# Sheet1.net
KiCad netlist of a schematic drawn in Altium Designer
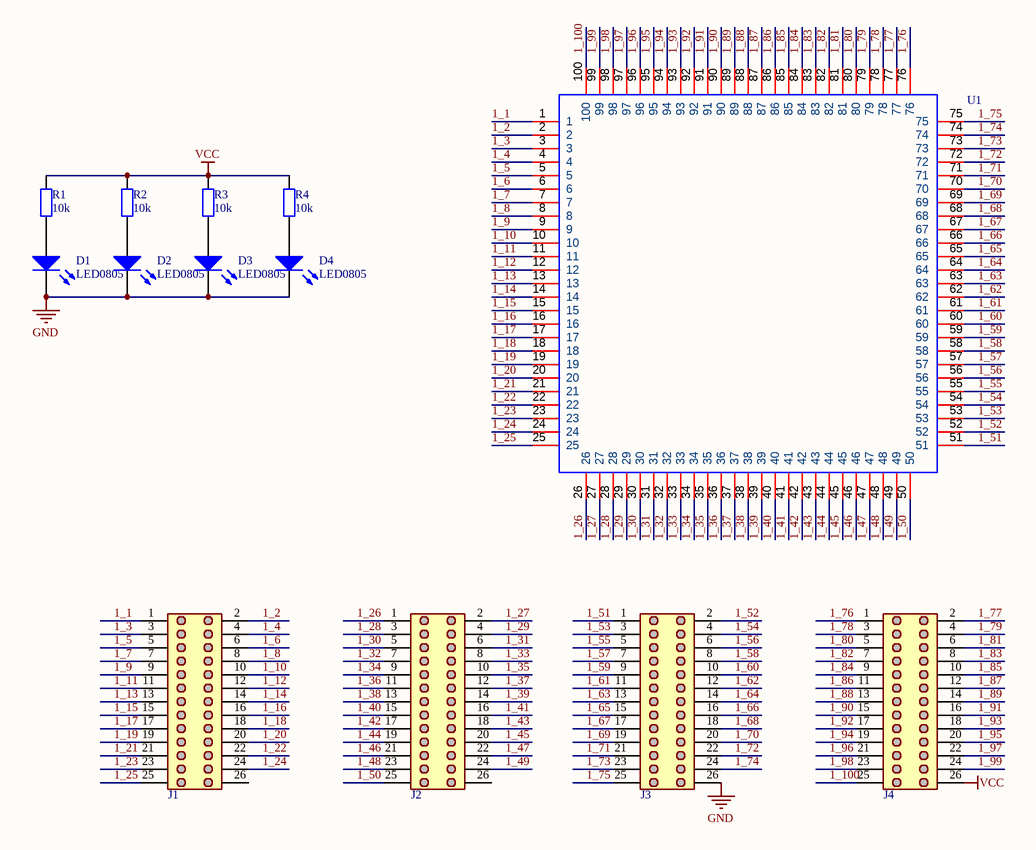
[diagram p0: Sheet1.SchDoc]

(export (version "E")
  (design (tool "Eeschema 10.0.6"))
  (components
    (comp (ref "D1") (value "LED0805") (footprint "L0805RED") (libsource (lib "SMDLibrary") (part "LED0805")))
    (comp (ref "D2") (value "LED0805") (footprint "L0805RED") (libsource (lib "SMDLibrary") (part "LED0805")))
    (comp (ref "D3") (value "LED0805") (footprint "L0805RED") (libsource (lib "SMDLibrary") (part "LED0805")))
    (comp (ref "D4") (value "LED0805") (footprint "L0805RED") (libsource (lib "SMDLibrary") (part "LED0805")))
    (comp (ref "J1")
      (value "Header 13x2 TH Pitch 2.54mm")
      (footprint "Header 13x2 TH Pitch 2.54mm")
      (libsource (lib "SMDLibrary") (part "Header 13x2 TH Pitch 2.54mm"))
    )
    (comp (ref "J2")
      (value "Header 13x2 TH Pitch 2.54mm")
      (footprint "Header 13x2 TH Pitch 2.54mm")
      (libsource (lib "SMDLibrary") (part "Header 13x2 TH Pitch 2.54mm"))
    )
    (comp (ref "J3")
      (value "Header 13x2 TH Pitch 2.54mm")
      (footprint "Header 13x2 TH Pitch 2.54mm")
      (libsource (lib "SMDLibrary") (part "Header 13x2 TH Pitch 2.54mm"))
    )
    (comp (ref "J4")
      (value "Header 13x2 TH Pitch 2.54mm")
      (footprint "Header 13x2 TH Pitch 2.54mm")
      (libsource (lib "SMDLibrary") (part "Header 13x2 TH Pitch 2.54mm"))
    )
    (comp (ref "R1") (value "10k") (footprint "R0805") (libsource (lib "SMDLibrary") (part "Resistor")))
    (comp (ref "R2") (value "10k") (footprint "R0805") (libsource (lib "SMDLibrary") (part "Resistor")))
    (comp (ref "R3") (value "10k") (footprint "R0805") (libsource (lib "SMDLibrary") (part "Resistor")))
    (comp (ref "R4") (value "10k") (footprint "R0805") (libsource (lib "SMDLibrary") (part "Resistor")))
    (comp (ref "U1")
      (value "QFP100-0.5 SOCKET")
      (footprint "QFP100-0.5 SOCKET")
      (libsource (lib "SMDLibrary") (part "QFP100-0.5 SOCKET"))
    )
  )
  (nets
    (net (code "1") (name "/1_1") (class "Default")
      (node (ref "J1") (pin "1") (pinfunction "1_1") (pintype "passive"))
      (node (ref "U1") (pin "1") (pinfunction "1_1") (pintype "passive"))
    )
    (net (code "2") (name "/1_2") (class "Default")
      (node (ref "J1") (pin "2") (pinfunction "2_2") (pintype "passive"))
      (node (ref "U1") (pin "2") (pinfunction "2_2") (pintype "passive"))
    )
    (net (code "3") (name "/1_3") (class "Default")
      (node (ref "J1") (pin "3") (pinfunction "3_3") (pintype "passive"))
      (node (ref "U1") (pin "3") (pinfunction "3_3") (pintype "passive"))
    )
    (net (code "4") (name "/1_4") (class "Default")
      (node (ref "J1") (pin "4") (pinfunction "4_4") (pintype "passive"))
      (node (ref "U1") (pin "4") (pinfunction "4_4") (pintype "passive"))
    )
    (net (code "5") (name "/1_5") (class "Default")
      (node (ref "J1") (pin "5") (pinfunction "5_5") (pintype "passive"))
      (node (ref "U1") (pin "5") (pinfunction "5_5") (pintype "passive"))
    )
    (net (code "6") (name "/1_6") (class "Default")
      (node (ref "J1") (pin "6") (pinfunction "6_6") (pintype "passive"))
      (node (ref "U1") (pin "6") (pinfunction "6_6") (pintype "passive"))
    )
    (net (code "7") (name "/1_7") (class "Default")
      (node (ref "J1") (pin "7") (pinfunction "7_7") (pintype "passive"))
      (node (ref "U1") (pin "7") (pinfunction "7_7") (pintype "passive"))
    )
    (net (code "8") (name "/1_8") (class "Default")
      (node (ref "J1") (pin "8") (pinfunction "8_8") (pintype "passive"))
      (node (ref "U1") (pin "8") (pinfunction "8_8") (pintype "passive"))
    )
    (net (code "9") (name "/1_9") (class "Default")
      (node (ref "J1") (pin "9") (pinfunction "9_9") (pintype "passive"))
      (node (ref "U1") (pin "9") (pinfunction "9_9") (pintype "passive"))
    )
    (net (code "10") (name "/1_10") (class "Default")
      (node (ref "J1") (pin "10") (pinfunction "10_10") (pintype "passive"))
      (node (ref "U1") (pin "10") (pinfunction "10_10") (pintype "passive"))
    )
    (net (code "11") (name "/1_11") (class "Default")
      (node (ref "J1") (pin "11") (pinfunction "11_11") (pintype "passive"))
      (node (ref "U1") (pin "11") (pinfunction "11_11") (pintype "passive"))
    )
    (net (code "12") (name "/1_12") (class "Default")
      (node (ref "J1") (pin "12") (pinfunction "12_12") (pintype "passive"))
      (node (ref "U1") (pin "12") (pinfunction "12_12") (pintype "passive"))
    )
    (net (code "13") (name "/1_13") (class "Default")
      (node (ref "J1") (pin "13") (pinfunction "13_13") (pintype "passive"))
      (node (ref "U1") (pin "13") (pinfunction "13_13") (pintype "passive"))
    )
    (net (code "14") (name "/1_14") (class "Default")
      (node (ref "J1") (pin "14") (pinfunction "14_14") (pintype "passive"))
      (node (ref "U1") (pin "14") (pinfunction "14_14") (pintype "passive"))
    )
    (net (code "15") (name "/1_15") (class "Default")
      (node (ref "J1") (pin "15") (pinfunction "15_15") (pintype "passive"))
      (node (ref "U1") (pin "15") (pinfunction "15_15") (pintype "passive"))
    )
    (net (code "16") (name "/1_16") (class "Default")
      (node (ref "J1") (pin "16") (pinfunction "16_16") (pintype "passive"))
      (node (ref "U1") (pin "16") (pinfunction "16_16") (pintype "passive"))
    )
    (net (code "17") (name "/1_17") (class "Default")
      (node (ref "J1") (pin "17") (pinfunction "17_17") (pintype "passive"))
      (node (ref "U1") (pin "17") (pinfunction "17_17") (pintype "passive"))
    )
    (net (code "18") (name "/1_18") (class "Default")
      (node (ref "J1") (pin "18") (pinfunction "18_18") (pintype "passive"))
      (node (ref "U1") (pin "18") (pinfunction "18_18") (pintype "passive"))
    )
    (net (code "19") (name "/1_19") (class "Default")
      (node (ref "J1") (pin "19") (pinfunction "19_19") (pintype "passive"))
      (node (ref "U1") (pin "19") (pinfunction "19_19") (pintype "passive"))
    )
    (net (code "20") (name "/1_20") (class "Default")
      (node (ref "J1") (pin "20") (pinfunction "20_20") (pintype "passive"))
      (node (ref "U1") (pin "20") (pinfunction "20_20") (pintype "passive"))
    )
    (net (code "21") (name "/1_21") (class "Default")
      (node (ref "J1") (pin "21") (pinfunction "21_21") (pintype "passive"))
      (node (ref "U1") (pin "21") (pinfunction "21_21") (pintype "passive"))
    )
    (net (code "22") (name "/1_22") (class "Default")
      (node (ref "J1") (pin "22") (pinfunction "22_22") (pintype "passive"))
      (node (ref "U1") (pin "22") (pinfunction "22_22") (pintype "passive"))
    )
    (net (code "23") (name "/1_23") (class "Default")
      (node (ref "J1") (pin "23") (pinfunction "23_23") (pintype "passive"))
      (node (ref "U1") (pin "23") (pinfunction "23_23") (pintype "passive"))
    )
    (net (code "24") (name "/1_24") (class "Default")
      (node (ref "J1") (pin "24") (pinfunction "24_24") (pintype "passive"))
      (node (ref "U1") (pin "24") (pinfunction "24_24") (pintype "passive"))
    )
    (net (code "25") (name "/1_25") (class "Default")
      (node (ref "J1") (pin "25") (pinfunction "25_25") (pintype "passive"))
      (node (ref "U1") (pin "25") (pinfunction "25_25") (pintype "passive"))
    )
    (net (code "26") (name "/1_26") (class "Default")
      (node (ref "J2") (pin "1") (pinfunction "1_1") (pintype "passive"))
      (node (ref "U1") (pin "26") (pinfunction "26_26") (pintype "passive"))
    )
    (net (code "27") (name "/1_27") (class "Default")
      (node (ref "J2") (pin "2") (pinfunction "2_2") (pintype "passive"))
      (node (ref "U1") (pin "27") (pinfunction "27_27") (pintype "passive"))
    )
    (net (code "28") (name "/1_28") (class "Default")
      (node (ref "J2") (pin "3") (pinfunction "3_3") (pintype "passive"))
      (node (ref "U1") (pin "28") (pinfunction "28_28") (pintype "passive"))
    )
    (net (code "29") (name "/1_29") (class "Default")
      (node (ref "J2") (pin "4") (pinfunction "4_4") (pintype "passive"))
      (node (ref "U1") (pin "29") (pinfunction "29_29") (pintype "passive"))
    )
    (net (code "30") (name "/1_30") (class "Default")
      (node (ref "J2") (pin "5") (pinfunction "5_5") (pintype "passive"))
      (node (ref "U1") (pin "30") (pinfunction "30_30") (pintype "passive"))
    )
    (net (code "31") (name "/1_31") (class "Default")
      (node (ref "J2") (pin "6") (pinfunction "6_6") (pintype "passive"))
      (node (ref "U1") (pin "31") (pinfunction "31_31") (pintype "passive"))
    )
    (net (code "32") (name "/1_32") (class "Default")
      (node (ref "J2") (pin "7") (pinfunction "7_7") (pintype "passive"))
      (node (ref "U1") (pin "32") (pinfunction "32_32") (pintype "passive"))
    )
    (net (code "33") (name "/1_33") (class "Default")
      (node (ref "J2") (pin "8") (pinfunction "8_8") (pintype "passive"))
      (node (ref "U1") (pin "33") (pinfunction "33_33") (pintype "passive"))
    )
    (net (code "34") (name "/1_34") (class "Default")
      (node (ref "J2") (pin "9") (pinfunction "9_9") (pintype "passive"))
      (node (ref "U1") (pin "34") (pinfunction "34_34") (pintype "passive"))
    )
    (net (code "35") (name "/1_35") (class "Default")
      (node (ref "J2") (pin "10") (pinfunction "10_10") (pintype "passive"))
      (node (ref "U1") (pin "35") (pinfunction "35_35") (pintype "passive"))
    )
    (net (code "36") (name "/1_36") (class "Default")
      (node (ref "J2") (pin "11") (pinfunction "11_11") (pintype "passive"))
      (node (ref "U1") (pin "36") (pinfunction "36_36") (pintype "passive"))
    )
    (net (code "37") (name "/1_37") (class "Default")
      (node (ref "J2") (pin "12") (pinfunction "12_12") (pintype "passive"))
      (node (ref "U1") (pin "37") (pinfunction "37_37") (pintype "passive"))
    )
    (net (code "38") (name "/1_38") (class "Default")
      (node (ref "J2") (pin "13") (pinfunction "13_13") (pintype "passive"))
      (node (ref "U1") (pin "38") (pinfunction "38_38") (pintype "passive"))
    )
    (net (code "39") (name "/1_39") (class "Default")
      (node (ref "J2") (pin "14") (pinfunction "14_14") (pintype "passive"))
      (node (ref "U1") (pin "39") (pinfunction "39_39") (pintype "passive"))
    )
    (net (code "40") (name "/1_40") (class "Default")
      (node (ref "J2") (pin "15") (pinfunction "15_15") (pintype "passive"))
      (node (ref "U1") (pin "40") (pinfunction "40_40") (pintype "passive"))
    )
    (net (code "41") (name "/1_41") (class "Default")
      (node (ref "J2") (pin "16") (pinfunction "16_16") (pintype "passive"))
      (node (ref "U1") (pin "41") (pinfunction "41_41") (pintype "passive"))
    )
    (net (code "42") (name "/1_42") (class "Default")
      (node (ref "J2") (pin "17") (pinfunction "17_17") (pintype "passive"))
      (node (ref "U1") (pin "42") (pinfunction "42_42") (pintype "passive"))
    )
    (net (code "43") (name "/1_43") (class "Default")
      (node (ref "J2") (pin "18") (pinfunction "18_18") (pintype "passive"))
      (node (ref "U1") (pin "43") (pinfunction "43_43") (pintype "passive"))
    )
    (net (code "44") (name "/1_44") (class "Default")
      (node (ref "J2") (pin "19") (pinfunction "19_19") (pintype "passive"))
      (node (ref "U1") (pin "44") (pinfunction "44_44") (pintype "passive"))
    )
    (net (code "45") (name "/1_45") (class "Default")
      (node (ref "J2") (pin "20") (pinfunction "20_20") (pintype "passive"))
      (node (ref "U1") (pin "45") (pinfunction "45_45") (pintype "passive"))
    )
    (net (code "46") (name "/1_46") (class "Default")
      (node (ref "J2") (pin "21") (pinfunction "21_21") (pintype "passive"))
      (node (ref "U1") (pin "46") (pinfunction "46_46") (pintype "passive"))
    )
    (net (code "47") (name "/1_47") (class "Default")
      (node (ref "J2") (pin "22") (pinfunction "22_22") (pintype "passive"))
      (node (ref "U1") (pin "47") (pinfunction "47_47") (pintype "passive"))
    )
    (net (code "48") (name "/1_48") (class "Default")
      (node (ref "J2") (pin "23") (pinfunction "23_23") (pintype "passive"))
      (node (ref "U1") (pin "48") (pinfunction "48_48") (pintype "passive"))
    )
    (net (code "49") (name "/1_49") (class "Default")
      (node (ref "J2") (pin "24") (pinfunction "24_24") (pintype "passive"))
      (node (ref "U1") (pin "49") (pinfunction "49_49") (pintype "passive"))
    )
    (net (code "50") (name "/1_50") (class "Default")
      (node (ref "J2") (pin "25") (pinfunction "25_25") (pintype "passive"))
      (node (ref "U1") (pin "50") (pinfunction "50_50") (pintype "passive"))
    )
    (net (code "51") (name "/1_51") (class "Default")
      (node (ref "J3") (pin "1") (pinfunction "1_1") (pintype "passive"))
      (node (ref "U1") (pin "51") (pinfunction "51_51") (pintype "passive"))
    )
    (net (code "52") (name "/1_52") (class "Default")
      (node (ref "J3") (pin "2") (pinfunction "2_2") (pintype "passive"))
      (node (ref "U1") (pin "52") (pinfunction "52_52") (pintype "passive"))
    )
    (net (code "53") (name "/1_53") (class "Default")
      (node (ref "J3") (pin "3") (pinfunction "3_3") (pintype "passive"))
      (node (ref "U1") (pin "53") (pinfunction "53_53") (pintype "passive"))
    )
    (net (code "54") (name "/1_54") (class "Default")
      (node (ref "J3") (pin "4") (pinfunction "4_4") (pintype "passive"))
      (node (ref "U1") (pin "54") (pinfunction "54_54") (pintype "passive"))
    )
    (net (code "55") (name "/1_55") (class "Default")
      (node (ref "J3") (pin "5") (pinfunction "5_5") (pintype "passive"))
      (node (ref "U1") (pin "55") (pinfunction "55_55") (pintype "passive"))
    )
    (net (code "56") (name "/1_56") (class "Default")
      (node (ref "J3") (pin "6") (pinfunction "6_6") (pintype "passive"))
      (node (ref "U1") (pin "56") (pinfunction "56_56") (pintype "passive"))
    )
    (net (code "57") (name "/1_57") (class "Default")
      (node (ref "J3") (pin "7") (pinfunction "7_7") (pintype "passive"))
      (node (ref "U1") (pin "57") (pinfunction "57_57") (pintype "passive"))
    )
    (net (code "58") (name "/1_58") (class "Default")
      (node (ref "J3") (pin "8") (pinfunction "8_8") (pintype "passive"))
      (node (ref "U1") (pin "58") (pinfunction "58_58") (pintype "passive"))
    )
    (net (code "59") (name "/1_59") (class "Default")
      (node (ref "J3") (pin "9") (pinfunction "9_9") (pintype "passive"))
      (node (ref "U1") (pin "59") (pinfunction "59_59") (pintype "passive"))
    )
    (net (code "60") (name "/1_60") (class "Default")
      (node (ref "J3") (pin "10") (pinfunction "10_10") (pintype "passive"))
      (node (ref "U1") (pin "60") (pinfunction "60_60") (pintype "passive"))
    )
    (net (code "61") (name "/1_61") (class "Default")
      (node (ref "J3") (pin "11") (pinfunction "11_11") (pintype "passive"))
      (node (ref "U1") (pin "61") (pinfunction "61_61") (pintype "passive"))
    )
    (net (code "62") (name "/1_62") (class "Default")
      (node (ref "J3") (pin "12") (pinfunction "12_12") (pintype "passive"))
      (node (ref "U1") (pin "62") (pinfunction "62_62") (pintype "passive"))
    )
    (net (code "63") (name "/1_63") (class "Default")
      (node (ref "J3") (pin "13") (pinfunction "13_13") (pintype "passive"))
      (node (ref "U1") (pin "63") (pinfunction "63_63") (pintype "passive"))
    )
    (net (code "64") (name "/1_64") (class "Default")
      (node (ref "J3") (pin "14") (pinfunction "14_14") (pintype "passive"))
      (node (ref "U1") (pin "64") (pinfunction "64_64") (pintype "passive"))
    )
    (net (code "65") (name "/1_65") (class "Default")
      (node (ref "J3") (pin "15") (pinfunction "15_15") (pintype "passive"))
      (node (ref "U1") (pin "65") (pinfunction "65_65") (pintype "passive"))
    )
    (net (code "66") (name "/1_66") (class "Default")
      (node (ref "J3") (pin "16") (pinfunction "16_16") (pintype "passive"))
      (node (ref "U1") (pin "66") (pinfunction "66_66") (pintype "passive"))
    )
    (net (code "67") (name "/1_67") (class "Default")
      (node (ref "J3") (pin "17") (pinfunction "17_17") (pintype "passive"))
      (node (ref "U1") (pin "67") (pinfunction "67_67") (pintype "passive"))
    )
    (net (code "68") (name "/1_68") (class "Default")
      (node (ref "J3") (pin "18") (pinfunction "18_18") (pintype "passive"))
      (node (ref "U1") (pin "68") (pinfunction "68_68") (pintype "passive"))
    )
    (net (code "69") (name "/1_69") (class "Default")
      (node (ref "J3") (pin "19") (pinfunction "19_19") (pintype "passive"))
      (node (ref "U1") (pin "69") (pinfunction "69_69") (pintype "passive"))
    )
    (net (code "70") (name "/1_70") (class "Default")
      (node (ref "J3") (pin "20") (pinfunction "20_20") (pintype "passive"))
      (node (ref "U1") (pin "70") (pinfunction "70_70") (pintype "passive"))
    )
    (net (code "71") (name "/1_71") (class "Default")
      (node (ref "J3") (pin "21") (pinfunction "21_21") (pintype "passive"))
      (node (ref "U1") (pin "71") (pinfunction "71_71") (pintype "passive"))
    )
    (net (code "72") (name "/1_72") (class "Default")
      (node (ref "J3") (pin "22") (pinfunction "22_22") (pintype "passive"))
      (node (ref "U1") (pin "72") (pinfunction "72_72") (pintype "passive"))
    )
    (net (code "73") (name "/1_73") (class "Default")
      (node (ref "J3") (pin "23") (pinfunction "23_23") (pintype "passive"))
      (node (ref "U1") (pin "73") (pinfunction "73_73") (pintype "passive"))
    )
    (net (code "74") (name "/1_74") (class "Default")
      (node (ref "J3") (pin "24") (pinfunction "24_24") (pintype "passive"))
      (node (ref "U1") (pin "74") (pinfunction "74_74") (pintype "passive"))
    )
    (net (code "75") (name "/1_75") (class "Default")
      (node (ref "J3") (pin "25") (pinfunction "25_25") (pintype "passive"))
      (node (ref "U1") (pin "75") (pinfunction "75_75") (pintype "passive"))
    )
    (net (code "76") (name "/1_76") (class "Default")
      (node (ref "J4") (pin "1") (pinfunction "1_1") (pintype "passive"))
      (node (ref "U1") (pin "76") (pinfunction "76_76") (pintype "passive"))
    )
    (net (code "77") (name "/1_77") (class "Default")
      (node (ref "J4") (pin "2") (pinfunction "2_2") (pintype "passive"))
      (node (ref "U1") (pin "77") (pinfunction "77_77") (pintype "passive"))
    )
    (net (code "78") (name "/1_78") (class "Default")
      (node (ref "J4") (pin "3") (pinfunction "3_3") (pintype "passive"))
      (node (ref "U1") (pin "78") (pinfunction "78_78") (pintype "passive"))
    )
    (net (code "79") (name "/1_79") (class "Default")
      (node (ref "J4") (pin "4") (pinfunction "4_4") (pintype "passive"))
      (node (ref "U1") (pin "79") (pinfunction "79_79") (pintype "passive"))
    )
    (net (code "80") (name "/1_80") (class "Default")
      (node (ref "J4") (pin "5") (pinfunction "5_5") (pintype "passive"))
      (node (ref "U1") (pin "80") (pinfunction "80_80") (pintype "passive"))
    )
    (net (code "81") (name "/1_81") (class "Default")
      (node (ref "J4") (pin "6") (pinfunction "6_6") (pintype "passive"))
      (node (ref "U1") (pin "81") (pinfunction "81_81") (pintype "passive"))
    )
    (net (code "82") (name "/1_82") (class "Default")
      (node (ref "J4") (pin "7") (pinfunction "7_7") (pintype "passive"))
      (node (ref "U1") (pin "82") (pinfunction "82_82") (pintype "passive"))
    )
    (net (code "83") (name "/1_83") (class "Default")
      (node (ref "J4") (pin "8") (pinfunction "8_8") (pintype "passive"))
      (node (ref "U1") (pin "83") (pinfunction "83_83") (pintype "passive"))
    )
    (net (code "84") (name "/1_84") (class "Default")
      (node (ref "J4") (pin "9") (pinfunction "9_9") (pintype "passive"))
      (node (ref "U1") (pin "84") (pinfunction "84_84") (pintype "passive"))
    )
    (net (code "85") (name "/1_85") (class "Default")
      (node (ref "J4") (pin "10") (pinfunction "10_10") (pintype "passive"))
      (node (ref "U1") (pin "85") (pinfunction "85_85") (pintype "passive"))
    )
    (net (code "86") (name "/1_86") (class "Default")
      (node (ref "J4") (pin "11") (pinfunction "11_11") (pintype "passive"))
      (node (ref "U1") (pin "86") (pinfunction "86_86") (pintype "passive"))
    )
    (net (code "87") (name "/1_87") (class "Default")
      (node (ref "J4") (pin "12") (pinfunction "12_12") (pintype "passive"))
      (node (ref "U1") (pin "87") (pinfunction "87_87") (pintype "passive"))
    )
    (net (code "88") (name "/1_88") (class "Default")
      (node (ref "J4") (pin "13") (pinfunction "13_13") (pintype "passive"))
      (node (ref "U1") (pin "88") (pinfunction "88_88") (pintype "passive"))
    )
    (net (code "89") (name "/1_89") (class "Default")
      (node (ref "J4") (pin "14") (pinfunction "14_14") (pintype "passive"))
      (node (ref "U1") (pin "89") (pinfunction "89_89") (pintype "passive"))
    )
    (net (code "90") (name "/1_90") (class "Default")
      (node (ref "J4") (pin "15") (pinfunction "15_15") (pintype "passive"))
      (node (ref "U1") (pin "90") (pinfunction "90_90") (pintype "passive"))
    )
    (net (code "91") (name "/1_91") (class "Default")
      (node (ref "J4") (pin "16") (pinfunction "16_16") (pintype "passive"))
      (node (ref "U1") (pin "91") (pinfunction "91_91") (pintype "passive"))
    )
    (net (code "92") (name "/1_92") (class "Default")
      (node (ref "J4") (pin "17") (pinfunction "17_17") (pintype "passive"))
      (node (ref "U1") (pin "92") (pinfunction "92_92") (pintype "passive"))
    )
    (net (code "93") (name "/1_93") (class "Default")
      (node (ref "J4") (pin "18") (pinfunction "18_18") (pintype "passive"))
      (node (ref "U1") (pin "93") (pinfunction "93_93") (pintype "passive"))
    )
    (net (code "94") (name "/1_94") (class "Default")
      (node (ref "J4") (pin "19") (pinfunction "19_19") (pintype "passive"))
      (node (ref "U1") (pin "94") (pinfunction "94_94") (pintype "passive"))
    )
    (net (code "95") (name "/1_95") (class "Default")
      (node (ref "J4") (pin "20") (pinfunction "20_20") (pintype "passive"))
      (node (ref "U1") (pin "95") (pinfunction "95_95") (pintype "passive"))
    )
    (net (code "96") (name "/1_96") (class "Default")
      (node (ref "J4") (pin "21") (pinfunction "21_21") (pintype "passive"))
      (node (ref "U1") (pin "96") (pinfunction "96_96") (pintype "passive"))
    )
    (net (code "97") (name "/1_97") (class "Default")
      (node (ref "J4") (pin "22") (pinfunction "22_22") (pintype "passive"))
      (node (ref "U1") (pin "97") (pinfunction "97_97") (pintype "passive"))
    )
    (net (code "98") (name "/1_98") (class "Default")
      (node (ref "J4") (pin "23") (pinfunction "23_23") (pintype "passive"))
      (node (ref "U1") (pin "98") (pinfunction "98_98") (pintype "passive"))
    )
    (net (code "99") (name "/1_99") (class "Default")
      (node (ref "J4") (pin "24") (pinfunction "24_24") (pintype "passive"))
      (node (ref "U1") (pin "99") (pinfunction "99_99") (pintype "passive"))
    )
    (net (code "100") (name "/1_100") (class "Default")
      (node (ref "J4") (pin "25") (pinfunction "25_25") (pintype "passive"))
      (node (ref "U1") (pin "100") (pinfunction "100_100") (pintype "passive"))
    )
    (net (code "101") (name "GND") (class "Default")
      (node (ref "D1") (pin "2") (pinfunction "K_2") (pintype "passive"))
      (node (ref "D2") (pin "2") (pinfunction "K_2") (pintype "passive"))
      (node (ref "D3") (pin "2") (pinfunction "K_2") (pintype "passive"))
      (node (ref "D4") (pin "2") (pinfunction "K_2") (pintype "passive"))
      (node (ref "J3") (pin "26") (pinfunction "26_26") (pintype "passive"))
    )
    (net (code "102") (name "Net-(D1-A)") (class "Default")
      (node (ref "D1") (pin "1") (pinfunction "A_1") (pintype "passive"))
      (node (ref "R1") (pin "1") (pinfunction "1_1") (pintype "passive"))
    )
    (net (code "103") (name "Net-(D2-A)") (class "Default")
      (node (ref "D2") (pin "1") (pinfunction "A_1") (pintype "passive"))
      (node (ref "R2") (pin "1") (pinfunction "1_1") (pintype "passive"))
    )
    (net (code "104") (name "Net-(D3-A)") (class "Default")
      (node (ref "D3") (pin "1") (pinfunction "A_1") (pintype "passive"))
      (node (ref "R3") (pin "1") (pinfunction "1_1") (pintype "passive"))
    )
    (net (code "105") (name "Net-(D4-A)") (class "Default")
      (node (ref "D4") (pin "1") (pinfunction "A_1") (pintype "passive"))
      (node (ref "R4") (pin "1") (pinfunction "1_1") (pintype "passive"))
    )
    (net (code "106") (name "VCC") (class "Default")
      (node (ref "J4") (pin "26") (pinfunction "26_26") (pintype "passive"))
      (node (ref "R1") (pin "2") (pinfunction "2_2") (pintype "passive"))
      (node (ref "R2") (pin "2") (pinfunction "2_2") (pintype "passive"))
      (node (ref "R3") (pin "2") (pinfunction "2_2") (pintype "passive"))
      (node (ref "R4") (pin "2") (pinfunction "2_2") (pintype "passive"))
    )
    (net (code "107") (name "unconnected-(J1-Pad26)") (class "Default")
      (node (ref "J1") (pin "26") (pinfunction "26_26") (pintype "passive"))
    )
    (net (code "108") (name "unconnected-(J2-Pad26)") (class "Default")
      (node (ref "J2") (pin "26") (pinfunction "26_26") (pintype "passive"))
    )
  )
)
